# dataloggerver2_0.net
KiCad netlist of a schematic drawn in EAGLE
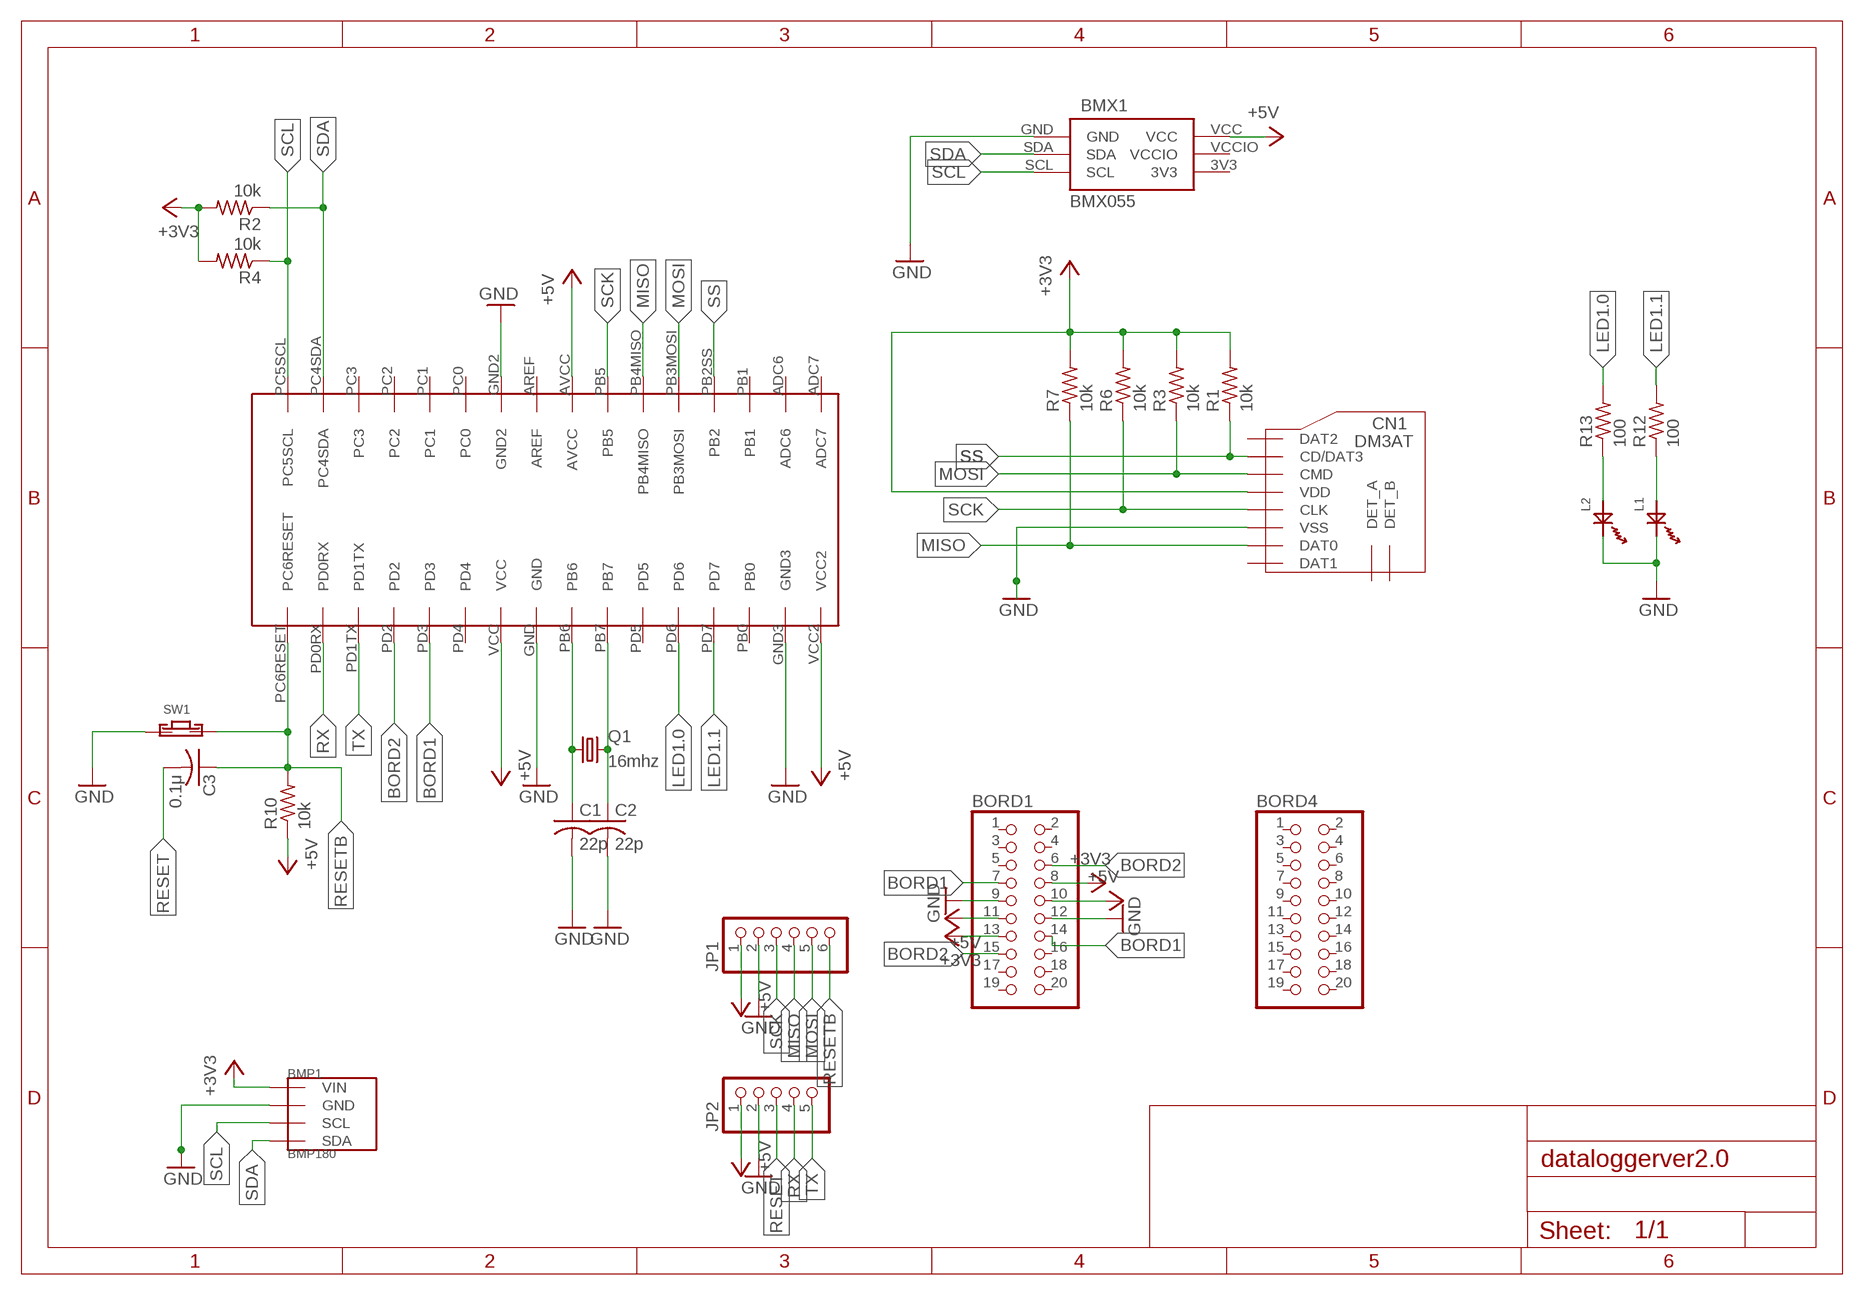
[diagram p0: schematic, sheet 1]

(export (version "E")
  (design (tool "Eeschema 10.0.6"))
  (components
    (comp (ref "BMP1")
      (value "BMP180")
      (footprint "eagle-import:GY-68")
      (libsource (lib "eagle-import") (part "BMP180"))
    )
    (comp (ref "BMX1")
      (value "BMX055")
      (footprint "eagle-import:BMX055")
      (libsource (lib "eagle-import") (part "BMX055"))
    )
    (comp (ref "BORD1")
      (value "PINHD-2X10/90")
      (footprint "eagle-import:2X10_90")
      (libsource (lib "eagle-import") (part "PINHD-2X10/90"))
    )
    (comp (ref "BORD4")
      (value "PINHD-2X10/90")
      (footprint "eagle-import:2X10_90")
      (libsource (lib "eagle-import") (part "PINHD-2X10/90"))
    )
    (comp (ref "C1")
      (value "22p")
      (footprint "eagle-import:C1608")
      (libsource (lib "eagle-import") (part "C-USC1608"))
    )
    (comp (ref "C2")
      (value "22p")
      (footprint "eagle-import:C1608")
      (libsource (lib "eagle-import") (part "C-USC1608"))
    )
    (comp (ref "C3")
      (value "0.1μ")
      (footprint "eagle-import:C1608")
      (libsource (lib "eagle-import") (part "C-USC1608"))
    )
    (comp (ref "CN1")
      (value "DM3AT")
      (footprint "eagle-import:DM3AT")
      (libsource (lib "eagle-import") (part "DM3AT"))
    )
    (comp (ref "JP1")
      (value "PINHD-1X6")
      (footprint "eagle-import:1X06")
      (libsource (lib "eagle-import") (part "PINHD-1X6"))
    )
    (comp (ref "JP2")
      (value "PINHD-1X5")
      (footprint "eagle-import:1X05")
      (libsource (lib "eagle-import") (part "PINHD-1X5"))
    )
    (comp (ref "L1")
      (value "OSXX1608C1A")
      (footprint "eagle-import:OSXX1608C1A")
      (libsource (lib "eagle-import") (part "OSXX1608C1A"))
    )
    (comp (ref "L2")
      (value "OSXX1608C1A")
      (footprint "eagle-import:OSXX1608C1A")
      (libsource (lib "eagle-import") (part "OSXX1608C1A"))
    )
    (comp (ref "Q1")
      (value "16mhz")
      (footprint "eagle-import:HC49UP")
      (libsource (lib "eagle-import") (part "CRYSTALHC49UP"))
    )
    (comp (ref "R1")
      (value "10k")
      (footprint "eagle-import:R0603")
      (libsource (lib "eagle-import") (part "R-US_R0603"))
    )
    (comp (ref "R2")
      (value "10k")
      (footprint "eagle-import:R0603")
      (libsource (lib "eagle-import") (part "R-US_R0603"))
    )
    (comp (ref "R3")
      (value "10k")
      (footprint "eagle-import:R0603")
      (libsource (lib "eagle-import") (part "R-US_R0603"))
    )
    (comp (ref "R4")
      (value "10k")
      (footprint "eagle-import:R0603")
      (libsource (lib "eagle-import") (part "R-US_R0603"))
    )
    (comp (ref "R6")
      (value "10k")
      (footprint "eagle-import:R0603")
      (libsource (lib "eagle-import") (part "R-US_R0603"))
    )
    (comp (ref "R7")
      (value "10k")
      (footprint "eagle-import:R0603")
      (libsource (lib "eagle-import") (part "R-US_R0603"))
    )
    (comp (ref "R10")
      (value "10k")
      (footprint "eagle-import:R0603")
      (libsource (lib "eagle-import") (part "R-US_R0603"))
    )
    (comp (ref "R12")
      (value "100")
      (footprint "eagle-import:R0603")
      (libsource (lib "eagle-import") (part "R-US_R0603"))
    )
    (comp (ref "R13")
      (value "100")
      (footprint "eagle-import:R0603")
      (libsource (lib "eagle-import") (part "R-US_R0603"))
    )
    (comp (ref "SW1")
      (value "TVAF06-A020B-R")
      (footprint "eagle-import:TVAF06-A020B-R")
      (libsource (lib "eagle-import") (part "TVAF06-A020B-R"))
    )
    (comp (ref "U$1")
      (value "ATMEGA328P-AU")
      (footprint "eagle-import:QFP80P900X900X120-32N")
      (libsource (lib "eagle-import") (part "ATMEGA328P-AU"))
    )
  )
  (nets
    (net (code "1") (name "+3V3") (class "Default")
      (node (ref "BMP1") (pin "P1") (pinfunction "VIN_P1") (pintype "bidirectional"))
      (node (ref "BORD1") (pin "13") (pinfunction "13_13") (pintype "passive"))
      (node (ref "BORD1") (pin "8") (pinfunction "8_8") (pintype "passive"))
      (node (ref "CN1") (pin "VDD") (pinfunction "VDD_VDD") (pintype "bidirectional"))
      (node (ref "R1") (pin "2") (pinfunction "2_2") (pintype "passive"))
      (node (ref "R2") (pin "2") (pinfunction "2_2") (pintype "passive"))
      (node (ref "R3") (pin "2") (pinfunction "2_2") (pintype "passive"))
      (node (ref "R4") (pin "2") (pinfunction "2_2") (pintype "passive"))
      (node (ref "R6") (pin "2") (pinfunction "2_2") (pintype "passive"))
      (node (ref "R7") (pin "2") (pinfunction "2_2") (pintype "passive"))
    )
    (net (code "2") (name "+5V") (class "Default")
      (node (ref "BMX1") (pin "VCC") (pinfunction "VCC_VCC") (pintype "power_in"))
      (node (ref "BORD1") (pin "10") (pinfunction "10_10") (pintype "passive"))
      (node (ref "BORD1") (pin "11") (pinfunction "11_11") (pintype "passive"))
      (node (ref "JP1") (pin "1") (pinfunction "1_1") (pintype "passive"))
      (node (ref "JP2") (pin "1") (pinfunction "1_1") (pintype "passive"))
      (node (ref "R10") (pin "1") (pinfunction "1_1") (pintype "passive"))
      (node (ref "U$1") (pin "AVCC") (pinfunction "AVCC_AVCC") (pintype "bidirectional"))
      (node (ref "U$1") (pin "VCC") (pinfunction "VCC_VCC") (pintype "bidirectional"))
      (node (ref "U$1") (pin "VCC2") (pinfunction "VCC2_VCC2") (pintype "bidirectional"))
    )
    (net (code "3") (name "/3V3") (class "Default")
      (node (ref "BMX1") (pin "3V3") (pinfunction "3V3_3V3") (pintype "power_in"))
    )
    (net (code "4") (name "/VCCIO") (class "Default")
      (node (ref "BMX1") (pin "VCCIO") (pinfunction "VCCIO_VCCIO") (pintype "power_in"))
    )
    (net (code "5") (name "BORD1") (class "Default")
      (node (ref "BORD1") (pin "14") (pinfunction "14_14") (pintype "passive"))
      (node (ref "BORD1") (pin "7") (pinfunction "7_7") (pintype "passive"))
      (node (ref "U$1") (pin "PD3") (pinfunction "PD3_PD3") (pintype "bidirectional"))
    )
    (net (code "6") (name "BORD2") (class "Default")
      (node (ref "BORD1") (pin "15") (pinfunction "15_15") (pintype "passive"))
      (node (ref "BORD1") (pin "6") (pinfunction "6_6") (pintype "passive"))
      (node (ref "U$1") (pin "PD2") (pinfunction "PD2_PD2") (pintype "bidirectional"))
    )
    (net (code "7") (name "GND") (class "Default")
      (node (ref "BMP1") (pin "P2") (pinfunction "GND_P2") (pintype "bidirectional"))
      (node (ref "BMX1") (pin "GND") (pinfunction "GND_GND") (pintype "power_in"))
      (node (ref "BORD1") (pin "12") (pinfunction "12_12") (pintype "passive"))
      (node (ref "BORD1") (pin "9") (pinfunction "9_9") (pintype "passive"))
      (node (ref "C1") (pin "2") (pinfunction "2_2") (pintype "passive"))
      (node (ref "C2") (pin "2") (pinfunction "2_2") (pintype "passive"))
      (node (ref "CN1") (pin "VSS") (pinfunction "VSS_VSS") (pintype "bidirectional"))
      (node (ref "JP1") (pin "2") (pinfunction "2_2") (pintype "passive"))
      (node (ref "JP2") (pin "2") (pinfunction "2_2") (pintype "passive"))
      (node (ref "L1") (pin "CT") (pinfunction "CT_CT") (pintype "bidirectional"))
      (node (ref "L2") (pin "CT") (pinfunction "CT_CT") (pintype "bidirectional"))
      (node (ref "SW1") (pin "P$1") (pinfunction "P$1_P$1") (pintype "bidirectional"))
      (node (ref "U$1") (pin "GND") (pinfunction "GND_GND") (pintype "bidirectional"))
      (node (ref "U$1") (pin "GND2") (pinfunction "GND2_GND2") (pintype "bidirectional"))
      (node (ref "U$1") (pin "GND3") (pinfunction "GND3_GND3") (pintype "bidirectional"))
    )
    (net (code "8") (name "LED1.0") (class "Default")
      (node (ref "R13") (pin "2") (pinfunction "2_2") (pintype "passive"))
      (node (ref "U$1") (pin "PD6") (pinfunction "PD6_PD6") (pintype "bidirectional"))
    )
    (net (code "9") (name "LED1.1") (class "Default")
      (node (ref "R12") (pin "2") (pinfunction "2_2") (pintype "passive"))
      (node (ref "U$1") (pin "PD7") (pinfunction "PD7_PD7") (pintype "bidirectional"))
    )
    (net (code "10") (name "MISO") (class "Default")
      (node (ref "CN1") (pin "DAT0") (pinfunction "DAT0_DAT0") (pintype "bidirectional"))
      (node (ref "JP1") (pin "4") (pinfunction "4_4") (pintype "passive"))
      (node (ref "R7") (pin "1") (pinfunction "1_1") (pintype "passive"))
      (node (ref "U$1") (pin "PB4MISO") (pinfunction "PB4MISO_PB4MISO") (pintype "bidirectional"))
    )
    (net (code "11") (name "MOSI") (class "Default")
      (node (ref "CN1") (pin "CMD") (pinfunction "CMD_CMD") (pintype "bidirectional"))
      (node (ref "JP1") (pin "5") (pinfunction "5_5") (pintype "passive"))
      (node (ref "R3") (pin "1") (pinfunction "1_1") (pintype "passive"))
      (node (ref "U$1") (pin "PB3MOSI") (pinfunction "PB3MOSI_PB3MOSI") (pintype "bidirectional"))
    )
    (net (code "12") (name "Net-(C1-Pad1)") (class "Default")
      (node (ref "C1") (pin "1") (pinfunction "1_1") (pintype "passive"))
      (node (ref "Q1") (pin "1") (pinfunction "1_1") (pintype "passive"))
      (node (ref "U$1") (pin "PB6") (pinfunction "PB6_PB6") (pintype "bidirectional"))
    )
    (net (code "13") (name "Net-(C2-Pad1)") (class "Default")
      (node (ref "C2") (pin "1") (pinfunction "1_1") (pintype "passive"))
      (node (ref "Q1") (pin "2") (pinfunction "2_2") (pintype "passive"))
      (node (ref "U$1") (pin "PB7") (pinfunction "PB7_PB7") (pintype "bidirectional"))
    )
    (net (code "14") (name "Net-(L1-PadAN)") (class "Default")
      (node (ref "L1") (pin "AN") (pinfunction "AN_AN") (pintype "bidirectional"))
      (node (ref "R12") (pin "1") (pinfunction "1_1") (pintype "passive"))
    )
    (net (code "15") (name "Net-(L2-PadAN)") (class "Default")
      (node (ref "L2") (pin "AN") (pinfunction "AN_AN") (pintype "bidirectional"))
      (node (ref "R13") (pin "1") (pinfunction "1_1") (pintype "passive"))
    )
    (net (code "16") (name "RESET") (class "Default")
      (node (ref "C3") (pin "2") (pinfunction "2_2") (pintype "passive"))
      (node (ref "JP2") (pin "3") (pinfunction "3_3") (pintype "passive"))
    )
    (net (code "17") (name "RESETB") (class "Default")
      (node (ref "C3") (pin "1") (pinfunction "1_1") (pintype "passive"))
      (node (ref "JP1") (pin "6") (pinfunction "6_6") (pintype "passive"))
      (node (ref "R10") (pin "2") (pinfunction "2_2") (pintype "passive"))
      (node (ref "SW1") (pin "P$2") (pinfunction "P$2_P$2") (pintype "bidirectional"))
      (node (ref "U$1") (pin "PC6RESET") (pinfunction "PC6RESET_PC6RESET") (pintype "bidirectional"))
    )
    (net (code "18") (name "RX") (class "Default")
      (node (ref "JP2") (pin "4") (pinfunction "4_4") (pintype "passive"))
      (node (ref "U$1") (pin "PD0RX") (pinfunction "PD0RX_PD0RX") (pintype "bidirectional"))
    )
    (net (code "19") (name "SCK") (class "Default")
      (node (ref "CN1") (pin "CLK") (pinfunction "CLK_CLK") (pintype "bidirectional"))
      (node (ref "JP1") (pin "3") (pinfunction "3_3") (pintype "passive"))
      (node (ref "R6") (pin "1") (pinfunction "1_1") (pintype "passive"))
      (node (ref "U$1") (pin "PB5") (pinfunction "PB5_PB5") (pintype "bidirectional"))
    )
    (net (code "20") (name "SCL") (class "Default")
      (node (ref "BMP1") (pin "P3") (pinfunction "SCL_P3") (pintype "bidirectional"))
      (node (ref "BMX1") (pin "SCL") (pinfunction "SCL_SCL") (pintype "bidirectional"))
      (node (ref "R4") (pin "1") (pinfunction "1_1") (pintype "passive"))
      (node (ref "U$1") (pin "PC5SCL") (pinfunction "PC5SCL_PC5SCL") (pintype "bidirectional"))
    )
    (net (code "21") (name "SDA") (class "Default")
      (node (ref "BMP1") (pin "P4") (pinfunction "SDA_P4") (pintype "bidirectional"))
      (node (ref "BMX1") (pin "SDA") (pinfunction "SDA_SDA") (pintype "bidirectional"))
      (node (ref "R2") (pin "1") (pinfunction "1_1") (pintype "passive"))
      (node (ref "U$1") (pin "PC4SDA") (pinfunction "PC4SDA_PC4SDA") (pintype "bidirectional"))
    )
    (net (code "22") (name "SS") (class "Default")
      (node (ref "CN1") (pin "CD/DAT3") (pinfunction "CD/DAT3_CD/DAT3") (pintype "bidirectional"))
      (node (ref "R1") (pin "1") (pinfunction "1_1") (pintype "passive"))
      (node (ref "U$1") (pin "PB2SS") (pinfunction "PB2_PB2SS") (pintype "bidirectional"))
    )
    (net (code "23") (name "TX") (class "Default")
      (node (ref "JP2") (pin "5") (pinfunction "5_5") (pintype "passive"))
      (node (ref "U$1") (pin "PD1TX") (pinfunction "PD1TX_PD1TX") (pintype "bidirectional"))
    )
    (net (code "24") (name "unconnected-(BORD1-Pad1)") (class "Default")
      (node (ref "BORD1") (pin "1") (pinfunction "1_1") (pintype "passive"))
    )
    (net (code "25") (name "unconnected-(BORD1-Pad2)") (class "Default")
      (node (ref "BORD1") (pin "2") (pinfunction "2_2") (pintype "passive"))
    )
    (net (code "26") (name "unconnected-(BORD1-Pad3)") (class "Default")
      (node (ref "BORD1") (pin "3") (pinfunction "3_3") (pintype "passive"))
    )
    (net (code "27") (name "unconnected-(BORD1-Pad4)") (class "Default")
      (node (ref "BORD1") (pin "4") (pinfunction "4_4") (pintype "passive"))
    )
    (net (code "28") (name "unconnected-(BORD1-Pad5)") (class "Default")
      (node (ref "BORD1") (pin "5") (pinfunction "5_5") (pintype "passive"))
    )
    (net (code "29") (name "unconnected-(BORD1-Pad16)") (class "Default")
      (node (ref "BORD1") (pin "16") (pinfunction "16_16") (pintype "passive"))
    )
    (net (code "30") (name "unconnected-(BORD1-Pad17)") (class "Default")
      (node (ref "BORD1") (pin "17") (pinfunction "17_17") (pintype "passive"))
    )
    (net (code "31") (name "unconnected-(BORD1-Pad18)") (class "Default")
      (node (ref "BORD1") (pin "18") (pinfunction "18_18") (pintype "passive"))
    )
    (net (code "32") (name "unconnected-(BORD1-Pad19)") (class "Default")
      (node (ref "BORD1") (pin "19") (pinfunction "19_19") (pintype "passive"))
    )
    (net (code "33") (name "unconnected-(BORD1-Pad20)") (class "Default")
      (node (ref "BORD1") (pin "20") (pinfunction "20_20") (pintype "passive"))
    )
    (net (code "34") (name "unconnected-(BORD4-Pad1)") (class "Default")
      (node (ref "BORD4") (pin "1") (pinfunction "1_1") (pintype "passive"))
    )
    (net (code "35") (name "unconnected-(BORD4-Pad2)") (class "Default")
      (node (ref "BORD4") (pin "2") (pinfunction "2_2") (pintype "passive"))
    )
    (net (code "36") (name "unconnected-(BORD4-Pad3)") (class "Default")
      (node (ref "BORD4") (pin "3") (pinfunction "3_3") (pintype "passive"))
    )
    (net (code "37") (name "unconnected-(BORD4-Pad4)") (class "Default")
      (node (ref "BORD4") (pin "4") (pinfunction "4_4") (pintype "passive"))
    )
    (net (code "38") (name "unconnected-(BORD4-Pad5)") (class "Default")
      (node (ref "BORD4") (pin "5") (pinfunction "5_5") (pintype "passive"))
    )
    (net (code "39") (name "unconnected-(BORD4-Pad6)") (class "Default")
      (node (ref "BORD4") (pin "6") (pinfunction "6_6") (pintype "passive"))
    )
    (net (code "40") (name "unconnected-(BORD4-Pad7)") (class "Default")
      (node (ref "BORD4") (pin "7") (pinfunction "7_7") (pintype "passive"))
    )
    (net (code "41") (name "unconnected-(BORD4-Pad8)") (class "Default")
      (node (ref "BORD4") (pin "8") (pinfunction "8_8") (pintype "passive"))
    )
    (net (code "42") (name "unconnected-(BORD4-Pad9)") (class "Default")
      (node (ref "BORD4") (pin "9") (pinfunction "9_9") (pintype "passive"))
    )
    (net (code "43") (name "unconnected-(BORD4-Pad10)") (class "Default")
      (node (ref "BORD4") (pin "10") (pinfunction "10_10") (pintype "passive"))
    )
    (net (code "44") (name "unconnected-(BORD4-Pad11)") (class "Default")
      (node (ref "BORD4") (pin "11") (pinfunction "11_11") (pintype "passive"))
    )
    (net (code "45") (name "unconnected-(BORD4-Pad12)") (class "Default")
      (node (ref "BORD4") (pin "12") (pinfunction "12_12") (pintype "passive"))
    )
    (net (code "46") (name "unconnected-(BORD4-Pad13)") (class "Default")
      (node (ref "BORD4") (pin "13") (pinfunction "13_13") (pintype "passive"))
    )
    (net (code "47") (name "unconnected-(BORD4-Pad14)") (class "Default")
      (node (ref "BORD4") (pin "14") (pinfunction "14_14") (pintype "passive"))
    )
    (net (code "48") (name "unconnected-(BORD4-Pad15)") (class "Default")
      (node (ref "BORD4") (pin "15") (pinfunction "15_15") (pintype "passive"))
    )
    (net (code "49") (name "unconnected-(BORD4-Pad16)") (class "Default")
      (node (ref "BORD4") (pin "16") (pinfunction "16_16") (pintype "passive"))
    )
    (net (code "50") (name "unconnected-(BORD4-Pad17)") (class "Default")
      (node (ref "BORD4") (pin "17") (pinfunction "17_17") (pintype "passive"))
    )
    (net (code "51") (name "unconnected-(BORD4-Pad18)") (class "Default")
      (node (ref "BORD4") (pin "18") (pinfunction "18_18") (pintype "passive"))
    )
    (net (code "52") (name "unconnected-(BORD4-Pad19)") (class "Default")
      (node (ref "BORD4") (pin "19") (pinfunction "19_19") (pintype "passive"))
    )
    (net (code "53") (name "unconnected-(BORD4-Pad20)") (class "Default")
      (node (ref "BORD4") (pin "20") (pinfunction "20_20") (pintype "passive"))
    )
    (net (code "54") (name "unconnected-(CN1-PadDAT1)") (class "Default")
      (node (ref "CN1") (pin "DAT1") (pinfunction "DAT1_DAT1") (pintype "bidirectional"))
    )
    (net (code "55") (name "unconnected-(CN1-PadDAT2)") (class "Default")
      (node (ref "CN1") (pin "DAT2") (pinfunction "DAT2_DAT2") (pintype "bidirectional"))
    )
    (net (code "56") (name "unconnected-(CN1-PadDET_A)") (class "Default")
      (node (ref "CN1") (pin "DET_A") (pinfunction "DET_A_DET_A") (pintype "bidirectional"))
    )
    (net (code "57") (name "unconnected-(CN1-PadDET_B)") (class "Default")
      (node (ref "CN1") (pin "DET_B") (pinfunction "DET_B_DET_B") (pintype "bidirectional"))
    )
    (net (code "58") (name "unconnected-(U$1-PadADC6)") (class "Default")
      (node (ref "U$1") (pin "ADC6") (pinfunction "ADC6_ADC6") (pintype "bidirectional"))
    )
    (net (code "59") (name "unconnected-(U$1-PadADC7)") (class "Default")
      (node (ref "U$1") (pin "ADC7") (pinfunction "ADC7_ADC7") (pintype "bidirectional"))
    )
    (net (code "60") (name "unconnected-(U$1-PadAREF)") (class "Default")
      (node (ref "U$1") (pin "AREF") (pinfunction "AREF_AREF") (pintype "bidirectional"))
    )
    (net (code "61") (name "unconnected-(U$1-PadPB0)") (class "Default")
      (node (ref "U$1") (pin "PB0") (pinfunction "PB0_PB0") (pintype "bidirectional"))
    )
    (net (code "62") (name "unconnected-(U$1-PadPB1)") (class "Default")
      (node (ref "U$1") (pin "PB1") (pinfunction "PB1_PB1") (pintype "bidirectional"))
    )
    (net (code "63") (name "unconnected-(U$1-PadPC0)") (class "Default")
      (node (ref "U$1") (pin "PC0") (pinfunction "PC0_PC0") (pintype "bidirectional"))
    )
    (net (code "64") (name "unconnected-(U$1-PadPC1)") (class "Default")
      (node (ref "U$1") (pin "PC1") (pinfunction "PC1_PC1") (pintype "bidirectional"))
    )
    (net (code "65") (name "unconnected-(U$1-PadPC2)") (class "Default")
      (node (ref "U$1") (pin "PC2") (pinfunction "PC2_PC2") (pintype "bidirectional"))
    )
    (net (code "66") (name "unconnected-(U$1-PadPC3)") (class "Default")
      (node (ref "U$1") (pin "PC3") (pinfunction "PC3_PC3") (pintype "bidirectional"))
    )
    (net (code "67") (name "unconnected-(U$1-PadPD4)") (class "Default")
      (node (ref "U$1") (pin "PD4") (pinfunction "PD4_PD4") (pintype "bidirectional"))
    )
    (net (code "68") (name "unconnected-(U$1-PadPD5)") (class "Default")
      (node (ref "U$1") (pin "PD5") (pinfunction "PD5_PD5") (pintype "bidirectional"))
    )
  )
)
